# controls_rev_3.net
KiCad netlist of a schematic drawn in EAGLE
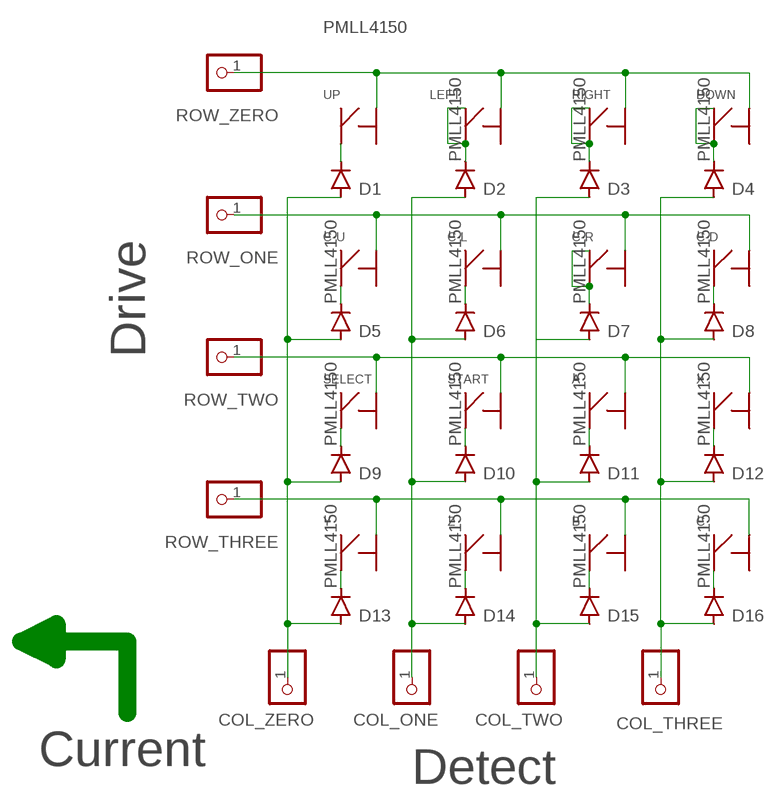
[diagram p0: schematic, sheet 1]

(export (version "E")
  (design (tool "Eeschema 10.0.6"))
  (components
    (comp (ref "A")
      (value "EVQQ2")
      (footprint "eagle-import:TACT")
      (libsource (lib "eagle-import") (part "EVQQ2"))
    )
    (comp (ref "B")
      (value "EVQQ2")
      (footprint "eagle-import:TACT")
      (libsource (lib "eagle-import") (part "EVQQ2"))
    )
    (comp (ref "C")
      (value "EVQQ2")
      (footprint "eagle-import:TACT")
      (libsource (lib "eagle-import") (part "EVQQ2"))
    )
    (comp (ref "C-D")
      (value "EVQQ2")
      (footprint "eagle-import:TACT")
      (libsource (lib "eagle-import") (part "EVQQ2"))
    )
    (comp (ref "C-L")
      (value "EVQQ2")
      (footprint "eagle-import:TACT")
      (libsource (lib "eagle-import") (part "EVQQ2"))
    )
    (comp (ref "C-R")
      (value "EVQQ2")
      (footprint "eagle-import:TACT")
      (libsource (lib "eagle-import") (part "EVQQ2"))
    )
    (comp (ref "C-U")
      (value "EVQQ2")
      (footprint "eagle-import:TACT")
      (libsource (lib "eagle-import") (part "EVQQ2"))
    )
    (comp (ref "COL_ONE")
      (value "PINHD-1X1")
      (footprint "eagle-import:1X01")
      (libsource (lib "eagle-import") (part "PINHD-1X1"))
    )
    (comp (ref "COL_THREE")
      (value "PINHD-1X1")
      (footprint "eagle-import:1X01")
      (libsource (lib "eagle-import") (part "PINHD-1X1"))
    )
    (comp (ref "COL_TWO")
      (value "PINHD-1X1")
      (footprint "eagle-import:1X01")
      (libsource (lib "eagle-import") (part "PINHD-1X1"))
    )
    (comp (ref "COL_ZERO")
      (value "PINHD-1X1")
      (footprint "eagle-import:1X01")
      (libsource (lib "eagle-import") (part "PINHD-1X1"))
    )
    (comp (ref "D1")
      (value "PMLL4150")
      (footprint "eagle-import:SOD80C")
      (libsource (lib "eagle-import") (part "PMLL4150"))
    )
    (comp (ref "D2")
      (value "PMLL4150")
      (footprint "eagle-import:SOD80C")
      (libsource (lib "eagle-import") (part "PMLL4150"))
    )
    (comp (ref "D3")
      (value "PMLL4150")
      (footprint "eagle-import:SOD80C")
      (libsource (lib "eagle-import") (part "PMLL4150"))
    )
    (comp (ref "D4")
      (value "PMLL4150")
      (footprint "eagle-import:SOD80C")
      (libsource (lib "eagle-import") (part "PMLL4150"))
    )
    (comp (ref "D5")
      (value "PMLL4150")
      (footprint "eagle-import:SOD80C")
      (libsource (lib "eagle-import") (part "PMLL4150"))
    )
    (comp (ref "D6")
      (value "PMLL4150")
      (footprint "eagle-import:SOD80C")
      (libsource (lib "eagle-import") (part "PMLL4150"))
    )
    (comp (ref "D7")
      (value "PMLL4150")
      (footprint "eagle-import:SOD80C")
      (libsource (lib "eagle-import") (part "PMLL4150"))
    )
    (comp (ref "D8")
      (value "PMLL4150")
      (footprint "eagle-import:SOD80C")
      (libsource (lib "eagle-import") (part "PMLL4150"))
    )
    (comp (ref "D9")
      (value "PMLL4150")
      (footprint "eagle-import:SOD80C")
      (libsource (lib "eagle-import") (part "PMLL4150"))
    )
    (comp (ref "D10")
      (value "PMLL4150")
      (footprint "eagle-import:SOD80C")
      (libsource (lib "eagle-import") (part "PMLL4150"))
    )
    (comp (ref "D11")
      (value "PMLL4150")
      (footprint "eagle-import:SOD80C")
      (libsource (lib "eagle-import") (part "PMLL4150"))
    )
    (comp (ref "D12")
      (value "PMLL4150")
      (footprint "eagle-import:SOD80C")
      (libsource (lib "eagle-import") (part "PMLL4150"))
    )
    (comp (ref "D13")
      (value "PMLL4150")
      (footprint "eagle-import:SOD80C")
      (libsource (lib "eagle-import") (part "PMLL4150"))
    )
    (comp (ref "D14")
      (value "PMLL4150")
      (footprint "eagle-import:SOD80C")
      (libsource (lib "eagle-import") (part "PMLL4150"))
    )
    (comp (ref "D15")
      (value "PMLL4150")
      (footprint "eagle-import:SOD80C")
      (libsource (lib "eagle-import") (part "PMLL4150"))
    )
    (comp (ref "D16")
      (value "PMLL4150")
      (footprint "eagle-import:SOD80C")
      (libsource (lib "eagle-import") (part "PMLL4150"))
    )
    (comp (ref "DOWN")
      (value "EVQQ2")
      (footprint "eagle-import:TACT")
      (libsource (lib "eagle-import") (part "EVQQ2"))
    )
    (comp (ref "LEFT")
      (value "EVQQ2")
      (footprint "eagle-import:TACT")
      (libsource (lib "eagle-import") (part "EVQQ2"))
    )
    (comp (ref "RIGHT")
      (value "EVQQ2")
      (footprint "eagle-import:TACT")
      (libsource (lib "eagle-import") (part "EVQQ2"))
    )
    (comp (ref "ROW_ONE")
      (value "PINHD-1X1")
      (footprint "eagle-import:1X01")
      (libsource (lib "eagle-import") (part "PINHD-1X1"))
    )
    (comp (ref "ROW_THREE")
      (value "PINHD-1X1")
      (footprint "eagle-import:1X01")
      (libsource (lib "eagle-import") (part "PINHD-1X1"))
    )
    (comp (ref "ROW_TWO")
      (value "PINHD-1X1")
      (footprint "eagle-import:1X01")
      (libsource (lib "eagle-import") (part "PINHD-1X1"))
    )
    (comp (ref "ROW_ZERO")
      (value "PINHD-1X1")
      (footprint "eagle-import:1X01")
      (libsource (lib "eagle-import") (part "PINHD-1X1"))
    )
    (comp (ref "SELECT")
      (value "EVQQ2")
      (footprint "eagle-import:TACT")
      (libsource (lib "eagle-import") (part "EVQQ2"))
    )
    (comp (ref "START")
      (value "EVQQ2")
      (footprint "eagle-import:TACT")
      (libsource (lib "eagle-import") (part "EVQQ2"))
    )
    (comp (ref "UP")
      (value "EVQQ2")
      (footprint "eagle-import:TACT")
      (libsource (lib "eagle-import") (part "EVQQ2"))
    )
    (comp (ref "X")
      (value "EVQQ2")
      (footprint "eagle-import:TACT")
      (libsource (lib "eagle-import") (part "EVQQ2"))
    )
    (comp (ref "Y")
      (value "EVQQ2")
      (footprint "eagle-import:TACT")
      (libsource (lib "eagle-import") (part "EVQQ2"))
    )
    (comp (ref "Z")
      (value "EVQQ2")
      (footprint "eagle-import:TACT")
      (libsource (lib "eagle-import") (part "EVQQ2"))
    )
  )
  (nets
    (net (code "1") (name "Net-(A-PIN0-PadPIN0@0)") (class "Default")
      (node (ref "A") (pin "PIN0@0") (pinfunction "PIN0_PIN0@0") (pintype "bidirectional"))
      (node (ref "D11") (pin "C") (pinfunction "C_C") (pintype "passive"))
    )
    (net (code "2") (name "Net-(A-PIN1-PadPIN1@1)") (class "Default")
      (node (ref "A") (pin "PIN1@1") (pinfunction "PIN1_PIN1@1") (pintype "bidirectional"))
      (node (ref "ROW_TWO") (pin "1") (pinfunction "1_1") (pintype "passive"))
      (node (ref "SELECT") (pin "PIN1@1") (pinfunction "PIN1_PIN1@1") (pintype "bidirectional"))
      (node (ref "START") (pin "PIN1@1") (pinfunction "PIN1_PIN1@1") (pintype "bidirectional"))
      (node (ref "X") (pin "PIN1@1") (pinfunction "PIN1_PIN1@1") (pintype "bidirectional"))
    )
    (net (code "3") (name "Net-(B-PIN0-PadPIN0@0)") (class "Default")
      (node (ref "B") (pin "PIN0@0") (pinfunction "PIN0_PIN0@0") (pintype "bidirectional"))
      (node (ref "D15") (pin "C") (pinfunction "C_C") (pintype "passive"))
    )
    (net (code "4") (name "Net-(B-PIN1-PadPIN1@1)") (class "Default")
      (node (ref "B") (pin "PIN1@1") (pinfunction "PIN1_PIN1@1") (pintype "bidirectional"))
      (node (ref "C") (pin "PIN1@1") (pinfunction "PIN1_PIN1@1") (pintype "bidirectional"))
      (node (ref "ROW_THREE") (pin "1") (pinfunction "1_1") (pintype "passive"))
      (node (ref "Y") (pin "PIN1@1") (pinfunction "PIN1_PIN1@1") (pintype "bidirectional"))
      (node (ref "Z") (pin "PIN1@1") (pinfunction "PIN1_PIN1@1") (pintype "bidirectional"))
    )
    (net (code "5") (name "Net-(C-D-PIN0-PadPIN0@0)") (class "Default")
      (node (ref "C-D") (pin "PIN0@0") (pinfunction "PIN0_PIN0@0") (pintype "bidirectional"))
      (node (ref "D8") (pin "C") (pinfunction "C_C") (pintype "passive"))
    )
    (net (code "6") (name "Net-(C-D-PIN1-PadPIN1@1)") (class "Default")
      (node (ref "C-D") (pin "PIN1@1") (pinfunction "PIN1_PIN1@1") (pintype "bidirectional"))
      (node (ref "C-L") (pin "PIN1@1") (pinfunction "PIN1_PIN1@1") (pintype "bidirectional"))
      (node (ref "C-R") (pin "PIN1@1") (pinfunction "PIN1_PIN1@1") (pintype "bidirectional"))
      (node (ref "C-U") (pin "PIN1@1") (pinfunction "PIN1_PIN1@1") (pintype "bidirectional"))
      (node (ref "ROW_ONE") (pin "1") (pinfunction "1_1") (pintype "passive"))
    )
    (net (code "7") (name "Net-(C-L-PIN0-PadPIN0@0)") (class "Default")
      (node (ref "C-L") (pin "PIN0@0") (pinfunction "PIN0_PIN0@0") (pintype "bidirectional"))
      (node (ref "D6") (pin "C") (pinfunction "C_C") (pintype "passive"))
    )
    (net (code "8") (name "Net-(C-PIN0-PadPIN0@0)") (class "Default")
      (node (ref "C") (pin "PIN0@0") (pinfunction "PIN0_PIN0@0") (pintype "bidirectional"))
      (node (ref "D16") (pin "C") (pinfunction "C_C") (pintype "passive"))
    )
    (net (code "9") (name "Net-(C-R-PIN0-PadPIN0@0)") (class "Default")
      (node (ref "C-R") (pin "PIN0@0") (pinfunction "PIN0_PIN0@0") (pintype "bidirectional"))
      (node (ref "C-R") (pin "PIN0@1") (pinfunction "PIN0_PIN0@1") (pintype "bidirectional"))
      (node (ref "D7") (pin "C") (pinfunction "C_C") (pintype "passive"))
    )
    (net (code "10") (name "Net-(C-U-PIN0-PadPIN0@0)") (class "Default")
      (node (ref "C-U") (pin "PIN0@0") (pinfunction "PIN0_PIN0@0") (pintype "bidirectional"))
      (node (ref "D5") (pin "C") (pinfunction "C_C") (pintype "passive"))
    )
    (net (code "11") (name "Net-(COL_ONE-Pad1)") (class "Default")
      (node (ref "COL_ONE") (pin "1") (pinfunction "1_1") (pintype "passive"))
      (node (ref "D10") (pin "A") (pinfunction "A_A") (pintype "passive"))
      (node (ref "D14") (pin "A") (pinfunction "A_A") (pintype "passive"))
      (node (ref "D2") (pin "A") (pinfunction "A_A") (pintype "passive"))
      (node (ref "D6") (pin "A") (pinfunction "A_A") (pintype "passive"))
    )
    (net (code "12") (name "Net-(COL_THREE-Pad1)") (class "Default")
      (node (ref "COL_THREE") (pin "1") (pinfunction "1_1") (pintype "passive"))
      (node (ref "D12") (pin "A") (pinfunction "A_A") (pintype "passive"))
      (node (ref "D16") (pin "A") (pinfunction "A_A") (pintype "passive"))
      (node (ref "D4") (pin "A") (pinfunction "A_A") (pintype "passive"))
      (node (ref "D8") (pin "A") (pinfunction "A_A") (pintype "passive"))
    )
    (net (code "13") (name "Net-(COL_TWO-Pad1)") (class "Default")
      (node (ref "COL_TWO") (pin "1") (pinfunction "1_1") (pintype "passive"))
      (node (ref "D11") (pin "A") (pinfunction "A_A") (pintype "passive"))
      (node (ref "D15") (pin "A") (pinfunction "A_A") (pintype "passive"))
      (node (ref "D3") (pin "A") (pinfunction "A_A") (pintype "passive"))
      (node (ref "D7") (pin "A") (pinfunction "A_A") (pintype "passive"))
    )
    (net (code "14") (name "Net-(COL_ZERO-Pad1)") (class "Default")
      (node (ref "COL_ZERO") (pin "1") (pinfunction "1_1") (pintype "passive"))
      (node (ref "D1") (pin "A") (pinfunction "A_A") (pintype "passive"))
      (node (ref "D13") (pin "A") (pinfunction "A_A") (pintype "passive"))
      (node (ref "D5") (pin "A") (pinfunction "A_A") (pintype "passive"))
      (node (ref "D9") (pin "A") (pinfunction "A_A") (pintype "passive"))
    )
    (net (code "15") (name "Net-(D1-PadC)") (class "Default")
      (node (ref "D1") (pin "C") (pinfunction "C_C") (pintype "passive"))
      (node (ref "UP") (pin "PIN0@0") (pinfunction "PIN0_PIN0@0") (pintype "bidirectional"))
    )
    (net (code "16") (name "Net-(D2-PadC)") (class "Default")
      (node (ref "D2") (pin "C") (pinfunction "C_C") (pintype "passive"))
      (node (ref "LEFT") (pin "PIN0@0") (pinfunction "PIN0_PIN0@0") (pintype "bidirectional"))
      (node (ref "LEFT") (pin "PIN0@1") (pinfunction "PIN0_PIN0@1") (pintype "bidirectional"))
    )
    (net (code "17") (name "Net-(D3-PadC)") (class "Default")
      (node (ref "D3") (pin "C") (pinfunction "C_C") (pintype "passive"))
      (node (ref "RIGHT") (pin "PIN0@0") (pinfunction "PIN0_PIN0@0") (pintype "bidirectional"))
      (node (ref "RIGHT") (pin "PIN0@1") (pinfunction "PIN0_PIN0@1") (pintype "bidirectional"))
    )
    (net (code "18") (name "Net-(D4-PadC)") (class "Default")
      (node (ref "D4") (pin "C") (pinfunction "C_C") (pintype "passive"))
      (node (ref "DOWN") (pin "PIN0@0") (pinfunction "PIN0_PIN0@0") (pintype "bidirectional"))
      (node (ref "DOWN") (pin "PIN0@1") (pinfunction "PIN0_PIN0@1") (pintype "bidirectional"))
    )
    (net (code "19") (name "Net-(D9-PadC)") (class "Default")
      (node (ref "D9") (pin "C") (pinfunction "C_C") (pintype "passive"))
      (node (ref "SELECT") (pin "PIN0@0") (pinfunction "PIN0_PIN0@0") (pintype "bidirectional"))
    )
    (net (code "20") (name "Net-(D10-PadC)") (class "Default")
      (node (ref "D10") (pin "C") (pinfunction "C_C") (pintype "passive"))
      (node (ref "START") (pin "PIN0@0") (pinfunction "PIN0_PIN0@0") (pintype "bidirectional"))
    )
    (net (code "21") (name "Net-(D12-PadC)") (class "Default")
      (node (ref "D12") (pin "C") (pinfunction "C_C") (pintype "passive"))
      (node (ref "X") (pin "PIN0@0") (pinfunction "PIN0_PIN0@0") (pintype "bidirectional"))
    )
    (net (code "22") (name "Net-(D13-PadC)") (class "Default")
      (node (ref "D13") (pin "C") (pinfunction "C_C") (pintype "passive"))
      (node (ref "Y") (pin "PIN0@0") (pinfunction "PIN0_PIN0@0") (pintype "bidirectional"))
    )
    (net (code "23") (name "Net-(D14-PadC)") (class "Default")
      (node (ref "D14") (pin "C") (pinfunction "C_C") (pintype "passive"))
      (node (ref "Z") (pin "PIN0@0") (pinfunction "PIN0_PIN0@0") (pintype "bidirectional"))
    )
    (net (code "24") (name "Net-(DOWN-PIN1-PadPIN1@1)") (class "Default")
      (node (ref "DOWN") (pin "PIN1@1") (pinfunction "PIN1_PIN1@1") (pintype "bidirectional"))
      (node (ref "LEFT") (pin "PIN1@1") (pinfunction "PIN1_PIN1@1") (pintype "bidirectional"))
      (node (ref "RIGHT") (pin "PIN1@1") (pinfunction "PIN1_PIN1@1") (pintype "bidirectional"))
      (node (ref "ROW_ZERO") (pin "1") (pinfunction "1_1") (pintype "passive"))
      (node (ref "UP") (pin "PIN1@1") (pinfunction "PIN1_PIN1@1") (pintype "bidirectional"))
    )
    (net (code "25") (name "unconnected-(A-PIN0-PadPIN0@1)") (class "Default")
      (node (ref "A") (pin "PIN0@1") (pinfunction "PIN0_PIN0@1") (pintype "bidirectional"))
    )
    (net (code "26") (name "unconnected-(A-PIN1-PadPIN1@0)") (class "Default")
      (node (ref "A") (pin "PIN1@0") (pinfunction "PIN1_PIN1@0") (pintype "bidirectional"))
    )
    (net (code "27") (name "unconnected-(B-PIN0-PadPIN0@1)") (class "Default")
      (node (ref "B") (pin "PIN0@1") (pinfunction "PIN0_PIN0@1") (pintype "bidirectional"))
    )
    (net (code "28") (name "unconnected-(B-PIN1-PadPIN1@0)") (class "Default")
      (node (ref "B") (pin "PIN1@0") (pinfunction "PIN1_PIN1@0") (pintype "bidirectional"))
    )
    (net (code "29") (name "unconnected-(C-D-PIN0-PadPIN0@1)") (class "Default")
      (node (ref "C-D") (pin "PIN0@1") (pinfunction "PIN0_PIN0@1") (pintype "bidirectional"))
    )
    (net (code "30") (name "unconnected-(C-D-PIN1-PadPIN1@0)") (class "Default")
      (node (ref "C-D") (pin "PIN1@0") (pinfunction "PIN1_PIN1@0") (pintype "bidirectional"))
    )
    (net (code "31") (name "unconnected-(C-L-PIN0-PadPIN0@1)") (class "Default")
      (node (ref "C-L") (pin "PIN0@1") (pinfunction "PIN0_PIN0@1") (pintype "bidirectional"))
    )
    (net (code "32") (name "unconnected-(C-L-PIN1-PadPIN1@0)") (class "Default")
      (node (ref "C-L") (pin "PIN1@0") (pinfunction "PIN1_PIN1@0") (pintype "bidirectional"))
    )
    (net (code "33") (name "unconnected-(C-PIN0-PadPIN0@1)") (class "Default")
      (node (ref "C") (pin "PIN0@1") (pinfunction "PIN0_PIN0@1") (pintype "bidirectional"))
    )
    (net (code "34") (name "unconnected-(C-PIN1-PadPIN1@0)") (class "Default")
      (node (ref "C") (pin "PIN1@0") (pinfunction "PIN1_PIN1@0") (pintype "bidirectional"))
    )
    (net (code "35") (name "unconnected-(C-R-PIN1-PadPIN1@0)") (class "Default")
      (node (ref "C-R") (pin "PIN1@0") (pinfunction "PIN1_PIN1@0") (pintype "bidirectional"))
    )
    (net (code "36") (name "unconnected-(C-U-PIN0-PadPIN0@1)") (class "Default")
      (node (ref "C-U") (pin "PIN0@1") (pinfunction "PIN0_PIN0@1") (pintype "bidirectional"))
    )
    (net (code "37") (name "unconnected-(C-U-PIN1-PadPIN1@0)") (class "Default")
      (node (ref "C-U") (pin "PIN1@0") (pinfunction "PIN1_PIN1@0") (pintype "bidirectional"))
    )
    (net (code "38") (name "unconnected-(DOWN-PIN1-PadPIN1@0)") (class "Default")
      (node (ref "DOWN") (pin "PIN1@0") (pinfunction "PIN1_PIN1@0") (pintype "bidirectional"))
    )
    (net (code "39") (name "unconnected-(LEFT-PIN1-PadPIN1@0)") (class "Default")
      (node (ref "LEFT") (pin "PIN1@0") (pinfunction "PIN1_PIN1@0") (pintype "bidirectional"))
    )
    (net (code "40") (name "unconnected-(RIGHT-PIN1-PadPIN1@0)") (class "Default")
      (node (ref "RIGHT") (pin "PIN1@0") (pinfunction "PIN1_PIN1@0") (pintype "bidirectional"))
    )
    (net (code "41") (name "unconnected-(SELECT-PIN0-PadPIN0@1)") (class "Default")
      (node (ref "SELECT") (pin "PIN0@1") (pinfunction "PIN0_PIN0@1") (pintype "bidirectional"))
    )
    (net (code "42") (name "unconnected-(SELECT-PIN1-PadPIN1@0)") (class "Default")
      (node (ref "SELECT") (pin "PIN1@0") (pinfunction "PIN1_PIN1@0") (pintype "bidirectional"))
    )
    (net (code "43") (name "unconnected-(START-PIN0-PadPIN0@1)") (class "Default")
      (node (ref "START") (pin "PIN0@1") (pinfunction "PIN0_PIN0@1") (pintype "bidirectional"))
    )
    (net (code "44") (name "unconnected-(START-PIN1-PadPIN1@0)") (class "Default")
      (node (ref "START") (pin "PIN1@0") (pinfunction "PIN1_PIN1@0") (pintype "bidirectional"))
    )
    (net (code "45") (name "unconnected-(UP-PIN0-PadPIN0@1)") (class "Default")
      (node (ref "UP") (pin "PIN0@1") (pinfunction "PIN0_PIN0@1") (pintype "bidirectional"))
    )
    (net (code "46") (name "unconnected-(UP-PIN1-PadPIN1@0)") (class "Default")
      (node (ref "UP") (pin "PIN1@0") (pinfunction "PIN1_PIN1@0") (pintype "bidirectional"))
    )
    (net (code "47") (name "unconnected-(X-PIN0-PadPIN0@1)") (class "Default")
      (node (ref "X") (pin "PIN0@1") (pinfunction "PIN0_PIN0@1") (pintype "bidirectional"))
    )
    (net (code "48") (name "unconnected-(X-PIN1-PadPIN1@0)") (class "Default")
      (node (ref "X") (pin "PIN1@0") (pinfunction "PIN1_PIN1@0") (pintype "bidirectional"))
    )
    (net (code "49") (name "unconnected-(Y-PIN0-PadPIN0@1)") (class "Default")
      (node (ref "Y") (pin "PIN0@1") (pinfunction "PIN0_PIN0@1") (pintype "bidirectional"))
    )
    (net (code "50") (name "unconnected-(Y-PIN1-PadPIN1@0)") (class "Default")
      (node (ref "Y") (pin "PIN1@0") (pinfunction "PIN1_PIN1@0") (pintype "bidirectional"))
    )
    (net (code "51") (name "unconnected-(Z-PIN0-PadPIN0@1)") (class "Default")
      (node (ref "Z") (pin "PIN0@1") (pinfunction "PIN0_PIN0@1") (pintype "bidirectional"))
    )
    (net (code "52") (name "unconnected-(Z-PIN1-PadPIN1@0)") (class "Default")
      (node (ref "Z") (pin "PIN1@0") (pinfunction "PIN1_PIN1@0") (pintype "bidirectional"))
    )
  )
)
